# Phase_Current_Voltage_Sense.net
KiCad netlist of a schematic drawn in Altium Designer
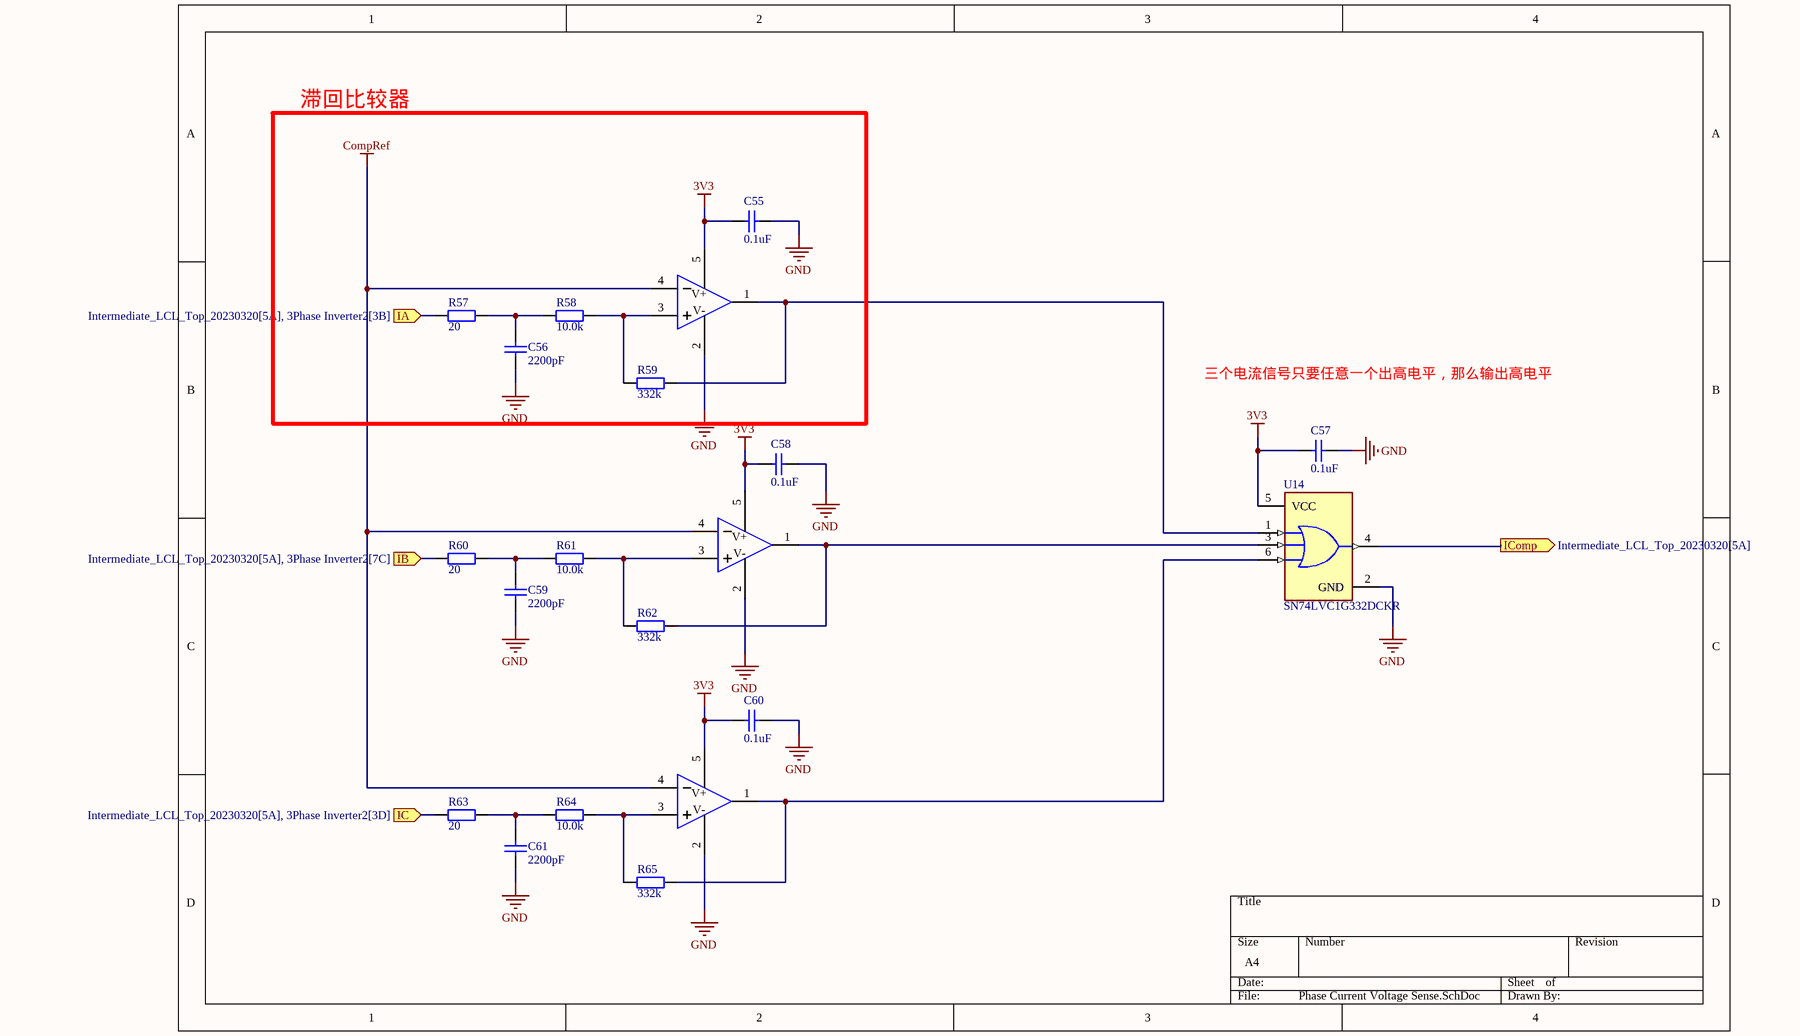
[diagram p0: Phase Current Voltage Sense.SchDoc]

(export (version "E")
  (design (tool "Eeschema 10.0.6"))
  (components
    (comp (ref "C55")
      (value "0.1uF")
      (footprint "CAPC1608X06N")
      (description "Capacitor")
      (fields (field (name "PUBLISHER") "Altium Limited"))
      (libsource (lib "Simscale") (part "Cap"))
    )
    (comp (ref "C56")
      (value "2200pF")
      (footprint "CAPC1608X06N")
      (description "Capacitor")
      (fields (field (name "PUBLISHER") "Altium Limited"))
      (libsource (lib "Simscale") (part "Cap"))
    )
    (comp (ref "C57")
      (value "0.1uF")
      (footprint "CAPC1608X06N")
      (description "Capacitor")
      (fields (field (name "PUBLISHER") "Altium Limited"))
      (libsource (lib "Simscale") (part "Cap"))
    )
    (comp (ref "C58")
      (value "0.1uF")
      (footprint "CAPC1608X06N")
      (description "Capacitor")
      (fields (field (name "PUBLISHER") "Altium Limited"))
      (libsource (lib "Simscale") (part "Cap"))
    )
    (comp (ref "C59")
      (value "2200pF")
      (footprint "CAPC1608X06N")
      (description "Capacitor")
      (fields (field (name "PUBLISHER") "Altium Limited"))
      (libsource (lib "Simscale") (part "Cap"))
    )
    (comp (ref "C60")
      (value "0.1uF")
      (footprint "CAPC1608X06N")
      (description "Capacitor")
      (fields (field (name "PUBLISHER") "Altium Limited"))
      (libsource (lib "Simscale") (part "Cap"))
    )
    (comp (ref "C61")
      (value "2200pF")
      (footprint "CAPC1608X06N")
      (description "Capacitor")
      (fields (field (name "PUBLISHER") "Altium Limited"))
      (libsource (lib "Simscale") (part "Cap"))
    )
    (comp (ref "R57")
      (value "20")
      (footprint "RESC1608X05N")
      (description "贴片电阻")
      (libsource (lib "Simscale") (part "0603 100KΩ (1003) 1%_4"))
    )
    (comp (ref "R58")
      (value "10.0k")
      (footprint "RESC1608X05N")
      (description "贴片电阻")
      (libsource (lib "Simscale") (part "0603 100KΩ (1003) 1%_4"))
    )
    (comp (ref "R59")
      (value "332k")
      (footprint "RESC1608X05N")
      (description "贴片电阻")
      (libsource (lib "Simscale") (part "0603 100KΩ (1003) 1%_4"))
    )
    (comp (ref "R60")
      (value "20")
      (footprint "RESC1608X05N")
      (description "贴片电阻")
      (libsource (lib "Simscale") (part "0603 100KΩ (1003) 1%_4"))
    )
    (comp (ref "R61")
      (value "10.0k")
      (footprint "RESC1608X05N")
      (description "贴片电阻")
      (libsource (lib "Simscale") (part "0603 100KΩ (1003) 1%_4"))
    )
    (comp (ref "R62")
      (value "332k")
      (footprint "RESC1608X05N")
      (description "贴片电阻")
      (libsource (lib "Simscale") (part "0603 100KΩ (1003) 1%_4"))
    )
    (comp (ref "R63")
      (value "20")
      (footprint "RESC1608X05N")
      (description "贴片电阻")
      (libsource (lib "Simscale") (part "0603 100KΩ (1003) 1%_4"))
    )
    (comp (ref "R64")
      (value "10.0k")
      (footprint "RESC1608X05N")
      (description "贴片电阻")
      (libsource (lib "Simscale") (part "0603 100KΩ (1003) 1%_4"))
    )
    (comp (ref "R65")
      (value "332k")
      (footprint "RESC1608X05N")
      (description "贴片电阻")
      (libsource (lib "Simscale") (part "0603 100KΩ (1003) 1%_4"))
    )
    (comp (ref "U13")
      (value "TLV3201AIDBVR")
      (footprint "SOT-23-5_L3.0-W1.7-P0.95-LS2.8-BR")
      (fields (field (name "MANUFACTURER") "TI(德州仪器)"))
      (libsource (lib "TLV3201AIDBVR1_TLV3201AIDBVR.schdoc") (part "TLV3201AIDBVR"))
    )
    (comp (ref "U14")
      (value "SN74LVC1G332DCKR")
      (footprint "FP-DCK0006A-MFG")
      (description "IC GATE OR 1CH 3-INP SC70-6")
      (fields
        (field (name "MANUFACTURER") "Texas Instruments")
        (field (name "OCTOPART") "https://octopart.com/sn74lvc1g332dckr-texas+instruments-464861")
      )
      (libsource (lib "Altium Content Vault") (part "a1fbee6839145229a27344b52c53a8d"))
    )
    (comp (ref "U15")
      (value "TLV3201AIDBVR")
      (footprint "SOT-23-5_L3.0-W1.7-P0.95-LS2.8-BR")
      (fields (field (name "MANUFACTURER") "TI(德州仪器)"))
      (libsource (lib "TLV3201AIDBVR1_TLV3201AIDBVR.schdoc") (part "TLV3201AIDBVR"))
    )
    (comp (ref "U16")
      (value "TLV3201AIDBVR")
      (footprint "SOT-23-5_L3.0-W1.7-P0.95-LS2.8-BR")
      (fields (field (name "MANUFACTURER") "TI(德州仪器)"))
      (libsource (lib "TLV3201AIDBVR1_TLV3201AIDBVR.schdoc") (part "TLV3201AIDBVR"))
    )
  )
  (nets
    (net (code "1") (name "/IA") (class "Default")
      (node (ref "R57") (pin "2") (pinfunction "2_2") (pintype "passive"))
    )
    (net (code "2") (name "/IB") (class "Default")
      (node (ref "R60") (pin "2") (pinfunction "2_2") (pintype "passive"))
    )
    (net (code "3") (name "/IC") (class "Default")
      (node (ref "R63") (pin "2") (pinfunction "2_2") (pintype "passive"))
    )
    (net (code "4") (name "/IComp") (class "Default")
      (node (ref "U14") (pin "4") (pinfunction "Y_4") (pintype "output"))
    )
    (net (code "5") (name "3V3") (class "Default")
      (node (ref "C55") (pin "1") (pinfunction "1_1") (pintype "passive"))
      (node (ref "C57") (pin "1") (pinfunction "1_1") (pintype "passive"))
      (node (ref "C58") (pin "1") (pinfunction "1_1") (pintype "passive"))
      (node (ref "C60") (pin "1") (pinfunction "1_1") (pintype "passive"))
      (node (ref "U13") (pin "5") (pinfunction "VCC_5") (pintype "passive"))
      (node (ref "U14") (pin "5") (pinfunction "VCC_5") (pintype "power_in"))
      (node (ref "U15") (pin "5") (pinfunction "VCC_5") (pintype "passive"))
      (node (ref "U16") (pin "5") (pinfunction "VCC_5") (pintype "passive"))
    )
    (net (code "6") (name "CompRef") (class "Default")
      (node (ref "U13") (pin "4") (pinfunction "IN-_4") (pintype "passive"))
      (node (ref "U15") (pin "4") (pinfunction "IN-_4") (pintype "passive"))
      (node (ref "U16") (pin "4") (pinfunction "IN-_4") (pintype "passive"))
    )
    (net (code "7") (name "GND") (class "Default")
      (node (ref "C55") (pin "2") (pinfunction "2_2") (pintype "passive"))
      (node (ref "C56") (pin "2") (pinfunction "2_2") (pintype "passive"))
      (node (ref "C57") (pin "2") (pinfunction "2_2") (pintype "passive"))
      (node (ref "C58") (pin "2") (pinfunction "2_2") (pintype "passive"))
      (node (ref "C59") (pin "2") (pinfunction "2_2") (pintype "passive"))
      (node (ref "C60") (pin "2") (pinfunction "2_2") (pintype "passive"))
      (node (ref "C61") (pin "2") (pinfunction "2_2") (pintype "passive"))
      (node (ref "U13") (pin "2") (pinfunction "GND_2") (pintype "passive"))
      (node (ref "U14") (pin "2") (pinfunction "GND_2") (pintype "power_in"))
      (node (ref "U15") (pin "2") (pinfunction "GND_2") (pintype "passive"))
      (node (ref "U16") (pin "2") (pinfunction "GND_2") (pintype "passive"))
    )
    (net (code "8") (name "Net-(C56-Pad1)") (class "Default")
      (node (ref "C56") (pin "1") (pinfunction "1_1") (pintype "passive"))
      (node (ref "R57") (pin "1") (pinfunction "1_1") (pintype "passive"))
      (node (ref "R58") (pin "2") (pinfunction "2_2") (pintype "passive"))
    )
    (net (code "9") (name "Net-(C59-Pad1)") (class "Default")
      (node (ref "C59") (pin "1") (pinfunction "1_1") (pintype "passive"))
      (node (ref "R60") (pin "1") (pinfunction "1_1") (pintype "passive"))
      (node (ref "R61") (pin "2") (pinfunction "2_2") (pintype "passive"))
    )
    (net (code "10") (name "Net-(C61-Pad1)") (class "Default")
      (node (ref "C61") (pin "1") (pinfunction "1_1") (pintype "passive"))
      (node (ref "R63") (pin "1") (pinfunction "1_1") (pintype "passive"))
      (node (ref "R64") (pin "2") (pinfunction "2_2") (pintype "passive"))
    )
    (net (code "11") (name "Net-(U13-IN+)") (class "Default")
      (node (ref "R58") (pin "1") (pinfunction "1_1") (pintype "passive"))
      (node (ref "R59") (pin "2") (pinfunction "2_2") (pintype "passive"))
      (node (ref "U13") (pin "3") (pinfunction "IN+_3") (pintype "passive"))
    )
    (net (code "12") (name "Net-(U13-OUT)") (class "Default")
      (node (ref "R59") (pin "1") (pinfunction "1_1") (pintype "passive"))
      (node (ref "U13") (pin "1") (pinfunction "OUT_1") (pintype "passive"))
      (node (ref "U14") (pin "1") (pinfunction "A_1") (pintype "input"))
    )
    (net (code "13") (name "Net-(U14-B)") (class "Default")
      (node (ref "R62") (pin "1") (pinfunction "1_1") (pintype "passive"))
      (node (ref "U14") (pin "3") (pinfunction "B_3") (pintype "input"))
      (node (ref "U15") (pin "1") (pinfunction "OUT_1") (pintype "passive"))
    )
    (net (code "14") (name "Net-(U14-C)") (class "Default")
      (node (ref "R65") (pin "1") (pinfunction "1_1") (pintype "passive"))
      (node (ref "U14") (pin "6") (pinfunction "C_6") (pintype "input"))
      (node (ref "U16") (pin "1") (pinfunction "OUT_1") (pintype "passive"))
    )
    (net (code "15") (name "Net-(U15-IN+)") (class "Default")
      (node (ref "R61") (pin "1") (pinfunction "1_1") (pintype "passive"))
      (node (ref "R62") (pin "2") (pinfunction "2_2") (pintype "passive"))
      (node (ref "U15") (pin "3") (pinfunction "IN+_3") (pintype "passive"))
    )
    (net (code "16") (name "Net-(U16-IN+)") (class "Default")
      (node (ref "R64") (pin "1") (pinfunction "1_1") (pintype "passive"))
      (node (ref "R65") (pin "2") (pinfunction "2_2") (pintype "passive"))
      (node (ref "U16") (pin "3") (pinfunction "IN+_3") (pintype "passive"))
    )
  )
)
